# 01-POWER.net
KiCad netlist of a schematic drawn in Altium Designer
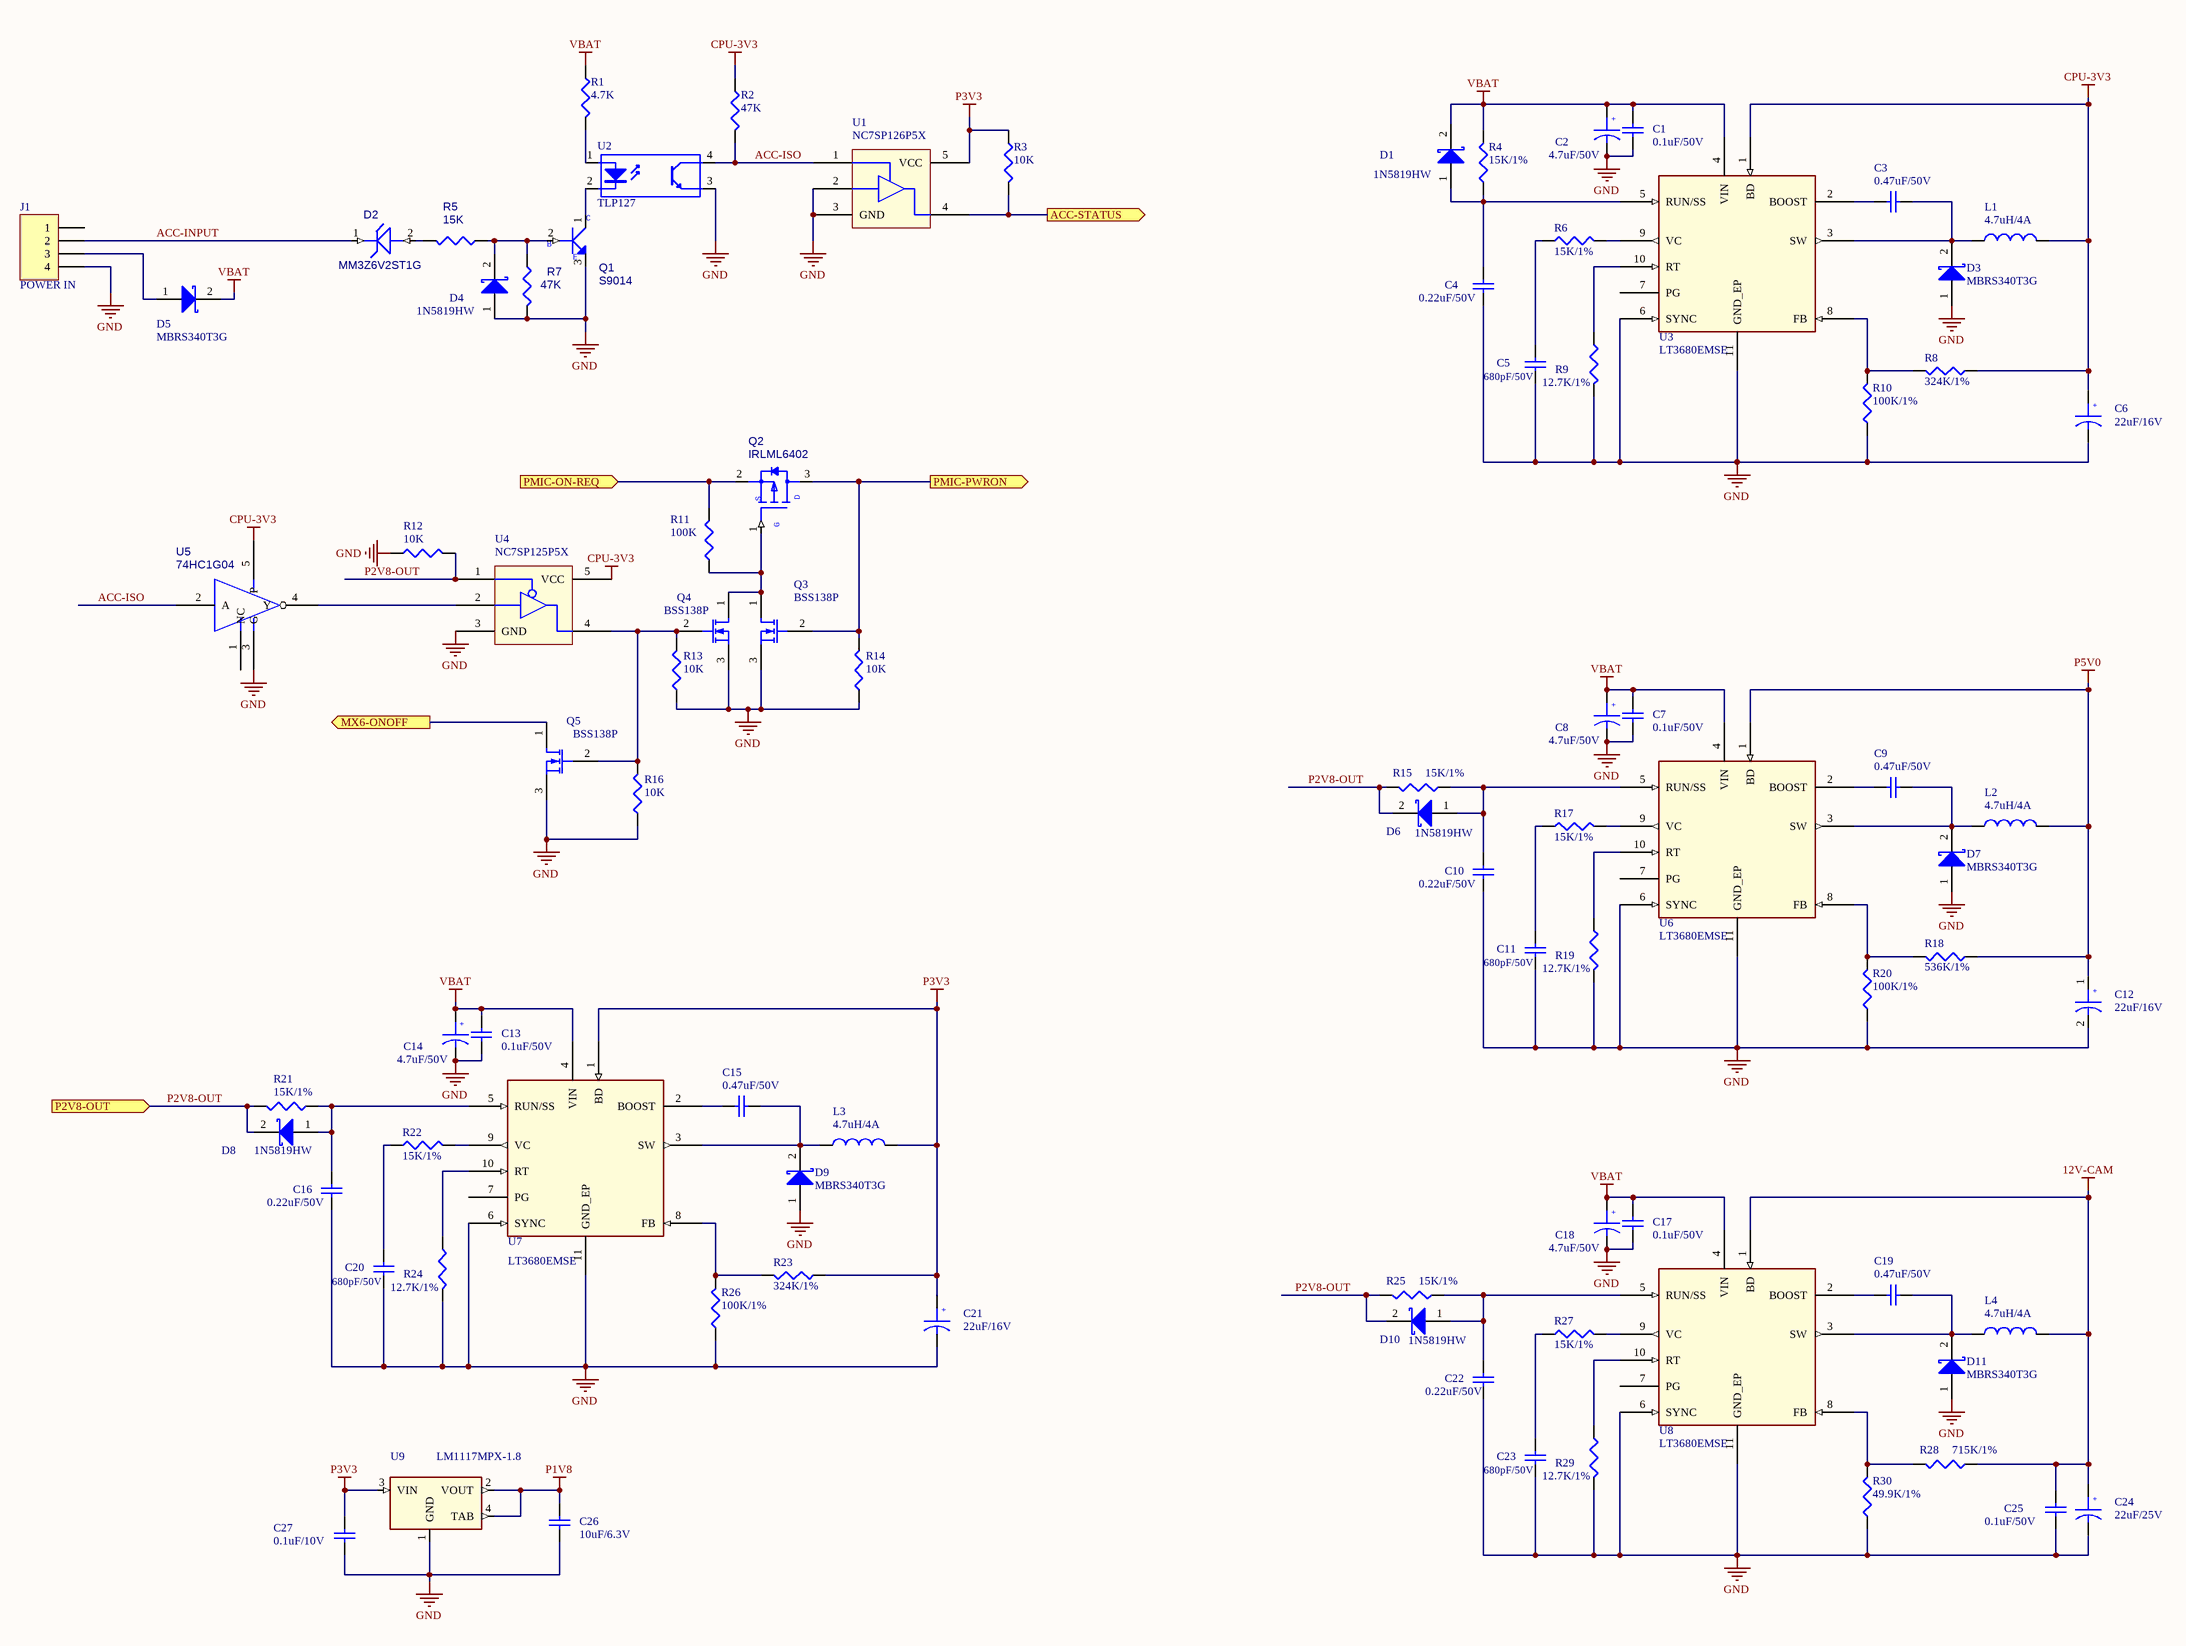
[diagram p0: 01-POWER.SchDoc]

(export (version "E")
  (design (tool "Eeschema 10.0.6"))
  (components
    (comp (ref "C1")
      (value "0.1uF/50V")
      (footprint "0603")
      (description "Capacitor")
      (fields (field (name "PUBLISHER") "Altium Limited"))
      (libsource (lib "Miscellaneous Devices") (part "Cap"))
    )
    (comp (ref "C2") (value "4.7uF/50V") (libsource (lib "*") (part "CAP WP")))
    (comp (ref "C3")
      (value "0.47uF/50V")
      (footprint "0603")
      (description "Capacitor")
      (fields (field (name "PUBLISHER") "Altium Limited"))
      (libsource (lib "Miscellaneous Devices") (part "Cap"))
    )
    (comp (ref "C4")
      (value "0.22uF/50V")
      (footprint "0603")
      (description "Capacitor")
      (fields (field (name "PUBLISHER") "Altium Limited"))
      (libsource (lib "Miscellaneous Devices") (part "Cap"))
    )
    (comp (ref "C5")
      (value "680pF/50V")
      (footprint "0402")
      (description "Capacitor")
      (fields (field (name "PUBLISHER") "Altium Limited"))
      (libsource (lib "Miscellaneous Devices") (part "Cap"))
    )
    (comp (ref "C6") (value "22uF/16V") (libsource (lib "*") (part "CAP WP")))
    (comp (ref "C7")
      (value "0.1uF/50V")
      (footprint "0603")
      (description "Capacitor")
      (fields (field (name "PUBLISHER") "Altium Limited"))
      (libsource (lib "Miscellaneous Devices") (part "Cap"))
    )
    (comp (ref "C8") (value "4.7uF/50V") (libsource (lib "*") (part "CAP WP")))
    (comp (ref "C9")
      (value "0.47uF/50V")
      (footprint "0603")
      (description "Capacitor")
      (fields (field (name "PUBLISHER") "Altium Limited"))
      (libsource (lib "Miscellaneous Devices") (part "Cap"))
    )
    (comp (ref "C10")
      (value "0.22uF/50V")
      (footprint "0603")
      (description "Capacitor")
      (fields (field (name "PUBLISHER") "Altium Limited"))
      (libsource (lib "Miscellaneous Devices") (part "Cap"))
    )
    (comp (ref "C11")
      (value "680pF/50V")
      (footprint "0402")
      (description "Capacitor")
      (fields (field (name "PUBLISHER") "Altium Limited"))
      (libsource (lib "Miscellaneous Devices") (part "Cap"))
    )
    (comp (ref "C12") (value "22uF/16V") (libsource (lib "") (part "CAP WP_1")))
    (comp (ref "C13")
      (value "0.1uF/50V")
      (footprint "0603")
      (description "Capacitor")
      (fields (field (name "PUBLISHER") "Altium Limited"))
      (libsource (lib "Miscellaneous Devices") (part "Cap"))
    )
    (comp (ref "C14") (value "4.7uF/50V") (libsource (lib "*") (part "CAP WP")))
    (comp (ref "C15")
      (value "0.47uF/50V")
      (footprint "0603")
      (description "Capacitor")
      (fields (field (name "PUBLISHER") "Altium Limited"))
      (libsource (lib "Miscellaneous Devices") (part "Cap"))
    )
    (comp (ref "C16")
      (value "0.22uF/50V")
      (footprint "0603")
      (description "Capacitor")
      (fields (field (name "PUBLISHER") "Altium Limited"))
      (libsource (lib "Miscellaneous Devices") (part "Cap"))
    )
    (comp (ref "C17")
      (value "0.1uF/50V")
      (footprint "0603")
      (description "Capacitor")
      (fields (field (name "PUBLISHER") "Altium Limited"))
      (libsource (lib "Miscellaneous Devices") (part "Cap"))
    )
    (comp (ref "C18") (value "4.7uF/50V") (libsource (lib "*") (part "CAP WP")))
    (comp (ref "C19")
      (value "0.47uF/50V")
      (footprint "0603")
      (description "Capacitor")
      (fields (field (name "PUBLISHER") "Altium Limited"))
      (libsource (lib "Miscellaneous Devices") (part "Cap"))
    )
    (comp (ref "C20")
      (value "680pF/50V")
      (footprint "0402")
      (description "Capacitor")
      (fields (field (name "PUBLISHER") "Altium Limited"))
      (libsource (lib "Miscellaneous Devices") (part "Cap"))
    )
    (comp (ref "C21") (value "22uF/16V") (libsource (lib "*") (part "CAP WP")))
    (comp (ref "C22")
      (value "0.22uF/50V")
      (footprint "0603")
      (description "Capacitor")
      (fields (field (name "PUBLISHER") "Altium Limited"))
      (libsource (lib "Miscellaneous Devices") (part "Cap"))
    )
    (comp (ref "C23")
      (value "680pF/50V")
      (footprint "0402")
      (description "Capacitor")
      (fields (field (name "PUBLISHER") "Altium Limited"))
      (libsource (lib "Miscellaneous Devices") (part "Cap"))
    )
    (comp (ref "C24") (value "22uF/25V") (libsource (lib "*") (part "CAP WP")))
    (comp (ref "C25")
      (value "0.1uF/50V")
      (footprint "0603")
      (description "Capacitor")
      (fields (field (name "PUBLISHER") "Altium Limited"))
      (libsource (lib "Miscellaneous Devices") (part "Cap"))
    )
    (comp (ref "C26")
      (value "10uF/6.3V")
      (footprint "0805")
      (description "Capacitor")
      (fields (field (name "PUBLISHER") "Altium Limited"))
      (libsource (lib "Miscellaneous Devices") (part "Cap"))
    )
    (comp (ref "C27")
      (value "0.1uF/10V")
      (footprint "0402")
      (description "Capacitor")
      (fields (field (name "PUBLISHER") "Altium Limited"))
      (libsource (lib "Miscellaneous Devices") (part "Cap"))
    )
    (comp (ref "D1")
      (value "1N5819HW")
      (footprint "1N5819")
      (description "Schottky Rectifier")
      (libsource (lib "Miscellaneous Devices") (part "Diode 11DQ03"))
    )
    (comp (ref "D2")
      (value "MM3Z6V2ST1G")
      (footprint "SOD323F")
      (libsource (lib "*") (part "MMGZ5231BPTLL34"))
    )
    (comp (ref "D3")
      (value "MBRS340T3G")
      (footprint "SMC")
      (description "Schottky Rectifier")
      (libsource (lib "Miscellaneous Devices") (part "Diode 11DQ03"))
    )
    (comp (ref "D4")
      (value "1N5819HW")
      (footprint "1N5819")
      (description "Schottky Rectifier")
      (libsource (lib "Miscellaneous Devices") (part "Diode 11DQ03"))
    )
    (comp (ref "D5")
      (value "MBRS340T3G")
      (footprint "SMC")
      (description "Schottky Rectifier")
      (libsource (lib "Miscellaneous Devices") (part "Diode 11DQ03"))
    )
    (comp (ref "D6")
      (value "1N5819HW")
      (footprint "1N5819")
      (description "Schottky Rectifier")
      (libsource (lib "Miscellaneous Devices") (part "Diode 11DQ03"))
    )
    (comp (ref "D7")
      (value "MBRS340T3G")
      (footprint "SMC")
      (description "Schottky Rectifier")
      (libsource (lib "Miscellaneous Devices") (part "Diode 11DQ03"))
    )
    (comp (ref "D8")
      (value "1N5819HW")
      (footprint "1N5819")
      (description "Schottky Rectifier")
      (libsource (lib "Miscellaneous Devices") (part "Diode 11DQ03"))
    )
    (comp (ref "D9")
      (value "MBRS340T3G")
      (footprint "SMC")
      (description "Schottky Rectifier")
      (libsource (lib "Miscellaneous Devices") (part "Diode 11DQ03"))
    )
    (comp (ref "D10")
      (value "1N5819HW")
      (footprint "1N5819")
      (description "Schottky Rectifier")
      (libsource (lib "Miscellaneous Devices") (part "Diode 11DQ03"))
    )
    (comp (ref "D11")
      (value "MBRS340T3G")
      (footprint "SMC")
      (description "Schottky Rectifier")
      (libsource (lib "Miscellaneous Devices") (part "Diode 11DQ03"))
    )
    (comp (ref "J1")
      (value "POWER IN")
      (footprint "3030WV-F-2*2P")
      (description "Header, 4-Pin")
      (fields (field (name "PUBLISHER") "Altium Limited"))
      (libsource (lib "Miscellaneous Connectors") (part "Header 4"))
    )
    (comp (ref "L1")
      (value "4.7uH/4A")
      (footprint "IND-10UH-1.5A")
      (description "IND CHK PWR 2.2UH@1MHZ 3.2A 20% SMT")
      (fields (field (name "TOLERANCE") "20%"))
      (libsource (lib "*") (part "INDUCTOR_A"))
    )
    (comp (ref "L2")
      (value "4.7uH/4A")
      (footprint "IND-10UH-1.5A")
      (description "IND CHK PWR 2.2UH@1MHZ 3.2A 20% SMT")
      (fields (field (name "TOLERANCE") "20%"))
      (libsource (lib "*") (part "INDUCTOR_A"))
    )
    (comp (ref "L3")
      (value "4.7uH/4A")
      (footprint "IND-10UH-1.5A")
      (description "IND CHK PWR 2.2UH@1MHZ 3.2A 20% SMT")
      (fields (field (name "TOLERANCE") "20%"))
      (libsource (lib "*") (part "INDUCTOR_A"))
    )
    (comp (ref "L4")
      (value "4.7uH/4A")
      (footprint "IND-10UH-1.5A")
      (description "IND CHK PWR 2.2UH@1MHZ 3.2A 20% SMT")
      (fields (field (name "TOLERANCE") "20%"))
      (libsource (lib "*") (part "INDUCTOR_A"))
    )
    (comp (ref "Q1")
      (value "S9014")
      (footprint "NPN")
      (fields (field (name "PART NUMBER") "SB039040000"))
      (libsource (lib "*") (part "MMBT3904_NL_SOT23-3"))
    )
    (comp (ref "Q2")
      (value "IRLML6402")
      (footprint "MOSFET")
      (fields (field (name "PART NUMBER") "SB934010010"))
      (libsource (lib "*") (part "AO3401L_SOT23-3_0"))
    )
    (comp (ref "Q3")
      (value "BSS138P")
      (footprint "NPN")
      (description "N-Channel MOSFET")
      (fields (field (name "PUBLISHER") "Altium Limited"))
      (libsource (lib "Miscellaneous Devices") (part "MOSFET-N"))
    )
    (comp (ref "Q4")
      (value "BSS138P")
      (footprint "NPN")
      (description "N-Channel MOSFET")
      (fields (field (name "PUBLISHER") "Altium Limited"))
      (libsource (lib "Miscellaneous Devices") (part "MOSFET-N"))
    )
    (comp (ref "Q5")
      (value "BSS138P")
      (footprint "NPN")
      (description "N-Channel MOSFET")
      (fields (field (name "PUBLISHER") "Altium Limited"))
      (libsource (lib "Miscellaneous Devices") (part "MOSFET-N"))
    )
    (comp (ref "R1") (value "4.7K") (footprint "0402") (libsource (lib "*") (part "CR16-1003FM")))
    (comp (ref "R2") (value "47K") (footprint "0402") (libsource (lib "*") (part "CR16-1003FM")))
    (comp (ref "R3") (value "10K") (footprint "0402") (libsource (lib "*") (part "CR16-1003FM")))
    (comp (ref "R4")
      (value "15K/1%")
      (footprint "0402")
      (description "Resistor")
      (fields (field (name "PUBLISHER") "Altium Limited"))
      (libsource (lib "Miscellaneous Devices") (part "Res3"))
    )
    (comp (ref "R5") (value "15K") (libsource (lib "*") (part "R")))
    (comp (ref "R6")
      (value "15K/1%")
      (footprint "0402")
      (description "Resistor")
      (fields (field (name "PUBLISHER") "Altium Limited"))
      (libsource (lib "Miscellaneous Devices") (part "Res3"))
    )
    (comp (ref "R7") (value "47K") (libsource (lib "*") (part "R")))
    (comp (ref "R8")
      (value "324K/1%")
      (footprint "0402")
      (description "Resistor")
      (fields (field (name "PUBLISHER") "Altium Limited"))
      (libsource (lib "Miscellaneous Devices") (part "Res3"))
    )
    (comp (ref "R9")
      (value "12.7K/1%")
      (footprint "0402")
      (description "Resistor")
      (fields (field (name "PUBLISHER") "Altium Limited"))
      (libsource (lib "Miscellaneous Devices") (part "Res3"))
    )
    (comp (ref "R10")
      (value "100K/1%")
      (footprint "0402")
      (description "Resistor")
      (fields (field (name "PUBLISHER") "Altium Limited"))
      (libsource (lib "Miscellaneous Devices") (part "Res3"))
    )
    (comp (ref "R11")
      (value "100K")
      (footprint "0402")
      (description "Resistor")
      (fields (field (name "PUBLISHER") "Altium Limited"))
      (libsource (lib "Miscellaneous Devices") (part "Res3"))
    )
    (comp (ref "R12") (value "10K") (footprint "0402") (libsource (lib "*") (part "CR16-1003FM")))
    (comp (ref "R13")
      (value "10K")
      (footprint "0402")
      (description "Resistor")
      (fields (field (name "PUBLISHER") "Altium Limited"))
      (libsource (lib "Miscellaneous Devices") (part "Res3"))
    )
    (comp (ref "R14")
      (value "10K")
      (footprint "0402")
      (description "Resistor")
      (fields (field (name "PUBLISHER") "Altium Limited"))
      (libsource (lib "Miscellaneous Devices") (part "Res3"))
    )
    (comp (ref "R15")
      (value "15K/1%")
      (footprint "0402")
      (description "Resistor")
      (fields (field (name "PUBLISHER") "Altium Limited"))
      (libsource (lib "Miscellaneous Devices") (part "Res3"))
    )
    (comp (ref "R16")
      (value "10K")
      (footprint "0402")
      (description "Resistor")
      (fields (field (name "PUBLISHER") "Altium Limited"))
      (libsource (lib "Miscellaneous Devices") (part "Res3"))
    )
    (comp (ref "R17")
      (value "15K/1%")
      (footprint "0402")
      (description "Resistor")
      (fields (field (name "PUBLISHER") "Altium Limited"))
      (libsource (lib "Miscellaneous Devices") (part "Res3"))
    )
    (comp (ref "R18")
      (value "536K/1%")
      (footprint "0402")
      (description "Resistor")
      (fields (field (name "PUBLISHER") "Altium Limited"))
      (libsource (lib "Miscellaneous Devices") (part "Res3"))
    )
    (comp (ref "R19")
      (value "12.7K/1%")
      (footprint "0402")
      (description "Resistor")
      (fields (field (name "PUBLISHER") "Altium Limited"))
      (libsource (lib "Miscellaneous Devices") (part "Res3"))
    )
    (comp (ref "R20")
      (value "100K/1%")
      (footprint "0402")
      (description "Resistor")
      (fields (field (name "PUBLISHER") "Altium Limited"))
      (libsource (lib "Miscellaneous Devices") (part "Res3"))
    )
    (comp (ref "R21")
      (value "15K/1%")
      (footprint "0402")
      (description "Resistor")
      (fields (field (name "PUBLISHER") "Altium Limited"))
      (libsource (lib "Miscellaneous Devices") (part "Res3"))
    )
    (comp (ref "R22")
      (value "15K/1%")
      (footprint "0402")
      (description "Resistor")
      (fields (field (name "PUBLISHER") "Altium Limited"))
      (libsource (lib "Miscellaneous Devices") (part "Res3"))
    )
    (comp (ref "R23")
      (value "324K/1%")
      (footprint "0402")
      (description "Resistor")
      (fields (field (name "PUBLISHER") "Altium Limited"))
      (libsource (lib "Miscellaneous Devices") (part "Res3"))
    )
    (comp (ref "R24")
      (value "12.7K/1%")
      (footprint "0402")
      (description "Resistor")
      (fields (field (name "PUBLISHER") "Altium Limited"))
      (libsource (lib "Miscellaneous Devices") (part "Res3"))
    )
    (comp (ref "R25")
      (value "15K/1%")
      (footprint "0402")
      (description "Resistor")
      (fields (field (name "PUBLISHER") "Altium Limited"))
      (libsource (lib "Miscellaneous Devices") (part "Res3"))
    )
    (comp (ref "R26")
      (value "100K/1%")
      (footprint "0402")
      (description "Resistor")
      (fields (field (name "PUBLISHER") "Altium Limited"))
      (libsource (lib "Miscellaneous Devices") (part "Res3"))
    )
    (comp (ref "R27")
      (value "15K/1%")
      (footprint "0402")
      (description "Resistor")
      (fields (field (name "PUBLISHER") "Altium Limited"))
      (libsource (lib "Miscellaneous Devices") (part "Res3"))
    )
    (comp (ref "R28")
      (value "715K/1%")
      (footprint "0402")
      (description "Resistor")
      (fields (field (name "PUBLISHER") "Altium Limited"))
      (libsource (lib "Miscellaneous Devices") (part "Res3"))
    )
    (comp (ref "R29")
      (value "12.7K/1%")
      (footprint "0402")
      (description "Resistor")
      (fields (field (name "PUBLISHER") "Altium Limited"))
      (libsource (lib "Miscellaneous Devices") (part "Res3"))
    )
    (comp (ref "R30")
      (value "49.9K/1%")
      (footprint "0402")
      (description "Resistor")
      (fields (field (name "PUBLISHER") "Altium Limited"))
      (libsource (lib "Miscellaneous Devices") (part "Res3"))
    )
    (comp (ref "U1") (value "NC7SP126P5X") (footprint "SC70") (libsource (lib "Schlib") (part "NC7SP126P5X")))
    (comp (ref "U2")
      (value "TLP127")
      (footprint "TLP127")
      (description "4-Pin Phototransistor Optocoupler")
      (fields (field (name "PUBLISHER") "Altium Limited"))
      (libsource (lib "Miscellaneous Devices") (part "Optoisolator1"))
    )
    (comp (ref "U3")
      (value "LT3680EMSE")
      (footprint "MSOP10")
      (description "IC VREG STEP DOWN SW 2.4MHZ 3.5A 0.79V-30V 3.6V-36V MSOP10")
      (libsource (lib "*") (part "LT3680_MSOP_10P"))
    )
    (comp (ref "U4") (value "NC7SP125P5X") (footprint "SC70") (libsource (lib "Schlib") (part "NC7SP125P5X")))
    (comp (ref "U5") (value "74HC1G04") (libsource (lib "*") (part "74LVC1G04GW_SOT353-5")))
    (comp (ref "U6")
      (value "LT3680EMSE")
      (footprint "MSOP10")
      (description "IC VREG STEP DOWN SW 2.4MHZ 3.5A 0.79V-30V 3.6V-36V MSOP10")
      (libsource (lib "*") (part "LT3680_MSOP_10P"))
    )
    (comp (ref "U7")
      (value "LT3680EMSE")
      (footprint "MSOP10")
      (description "IC VREG STEP DOWN SW 2.4MHZ 3.5A 0.79V-30V 3.6V-36V MSOP10")
      (libsource (lib "*") (part "LT3680_MSOP_10P"))
    )
    (comp (ref "U8")
      (value "LT3680EMSE")
      (footprint "MSOP10")
      (description "IC VREG STEP DOWN SW 2.4MHZ 3.5A 0.79V-30V 3.6V-36V MSOP10")
      (libsource (lib "*") (part "LT3680_MSOP_10P"))
    )
    (comp (ref "U9")
      (value "LM1117MPX-1.8")
      (footprint "AMS1117")
      (description "IC VREG LDO 1.8V 1A 10V SOT-223")
      (libsource (lib "*") (part "LD1117AS18"))
    )
  )
  (nets
    (net (code "1") (name "/ACC-INPUT") (class "Default")
      (node (ref "D2") (pin "1") (pinfunction "1_1") (pintype "input"))
      (node (ref "J1") (pin "2") (pinfunction "2_2") (pintype "passive"))
    )
    (net (code "2") (name "/ACC-ISO") (class "Default")
      (node (ref "R2") (pin "2") (pinfunction "2_2") (pintype "passive"))
      (node (ref "U1") (pin "1") (pinfunction "OE_1") (pintype "passive"))
      (node (ref "U2") (pin "4") (pinfunction "C_4") (pintype "passive"))
      (node (ref "U5") (pin "2") (pinfunction "A_2") (pintype "passive"))
    )
    (net (code "3") (name "/ACC-STATUS") (class "Default")
      (node (ref "R3") (pin "2") (pinfunction "2_2") (pintype "passive"))
      (node (ref "U1") (pin "4") (pinfunction "Y_4") (pintype "passive"))
    )
    (net (code "4") (name "/MX6-ONOFF") (class "Default")
      (node (ref "Q5") (pin "1") (pinfunction "D_1") (pintype "passive"))
    )
    (net (code "5") (name "/P2V8-OUT") (class "Default")
      (node (ref "D10") (pin "2") (pinfunction "K_2") (pintype "passive"))
      (node (ref "D6") (pin "2") (pinfunction "K_2") (pintype "passive"))
      (node (ref "D8") (pin "2") (pinfunction "K_2") (pintype "passive"))
      (node (ref "R12") (pin "1") (pinfunction "1_1") (pintype "passive"))
      (node (ref "R15") (pin "2") (pinfunction "2_2") (pintype "passive"))
      (node (ref "R21") (pin "2") (pinfunction "2_2") (pintype "passive"))
      (node (ref "R25") (pin "2") (pinfunction "2_2") (pintype "passive"))
      (node (ref "U4") (pin "1") (pinfunction "OE_1") (pintype "passive"))
    )
    (net (code "6") (name "/PMIC-ON-REQ") (class "Default")
      (node (ref "Q2") (pin "2") (pinfunction "S_2") (pintype "passive"))
      (node (ref "R11") (pin "1") (pinfunction "1_1") (pintype "passive"))
    )
    (net (code "7") (name "/PMIC-PWRON") (class "Default")
      (node (ref "Q2") (pin "3") (pinfunction "D_3") (pintype "passive"))
      (node (ref "Q3") (pin "2") (pinfunction "G_2") (pintype "passive"))
      (node (ref "R14") (pin "1") (pinfunction "1_1") (pintype "passive"))
    )
    (net (code "8") (name "12V-CAM") (class "Default")
      (node (ref "C24") (pin "1") (pinfunction "1_1") (pintype "passive"))
      (node (ref "C25") (pin "1") (pinfunction "1_1") (pintype "passive"))
      (node (ref "L4") (pin "2") (pinfunction "2_2") (pintype "passive"))
      (node (ref "R28") (pin "1") (pinfunction "1_1") (pintype "passive"))
      (node (ref "U8") (pin "1") (pinfunction "BD_1") (pintype "input"))
    )
    (net (code "9") (name "CPU-3V3") (class "Default")
      (node (ref "C6") (pin "1") (pinfunction "1_1") (pintype "passive"))
      (node (ref "L1") (pin "2") (pinfunction "2_2") (pintype "passive"))
      (node (ref "R2") (pin "1") (pinfunction "1_1") (pintype "passive"))
      (node (ref "R8") (pin "1") (pinfunction "1_1") (pintype "passive"))
      (node (ref "U3") (pin "1") (pinfunction "BD_1") (pintype "input"))
      (node (ref "U4") (pin "5") (pinfunction "VCC_5") (pintype "passive"))
      (node (ref "U5") (pin "5") (pinfunction "P_5") (pintype "passive"))
    )
    (net (code "10") (name "GND") (class "Default")
      (node (ref "C1") (pin "2") (pinfunction "2_2") (pintype "passive"))
      (node (ref "C10") (pin "2") (pinfunction "2_2") (pintype "passive"))
      (node (ref "C11") (pin "2") (pinfunction "2_2") (pintype "passive"))
      (node (ref "C12") (pin "2") (pinfunction "2_2") (pintype "passive"))
      (node (ref "C13") (pin "2") (pinfunction "2_2") (pintype "passive"))
      (node (ref "C14") (pin "2") (pinfunction "2_2") (pintype "passive"))
      (node (ref "C16") (pin "2") (pinfunction "2_2") (pintype "passive"))
      (node (ref "C17") (pin "2") (pinfunction "2_2") (pintype "passive"))
      (node (ref "C18") (pin "2") (pinfunction "2_2") (pintype "passive"))
      (node (ref "C2") (pin "2") (pinfunction "2_2") (pintype "passive"))
      (node (ref "C20") (pin "2") (pinfunction "2_2") (pintype "passive"))
      (node (ref "C21") (pin "2") (pinfunction "2_2") (pintype "passive"))
      (node (ref "C22") (pin "2") (pinfunction "2_2") (pintype "passive"))
      (node (ref "C23") (pin "2") (pinfunction "2_2") (pintype "passive"))
      (node (ref "C24") (pin "2") (pinfunction "2_2") (pintype "passive"))
      (node (ref "C25") (pin "2") (pinfunction "2_2") (pintype "passive"))
      (node (ref "C26") (pin "2") (pinfunction "2_2") (pintype "passive"))
      (node (ref "C27") (pin "2") (pinfunction "2_2") (pintype "passive"))
      (node (ref "C4") (pin "2") (pinfunction "2_2") (pintype "passive"))
      (node (ref "C5") (pin "2") (pinfunction "2_2") (pintype "passive"))
      (node (ref "C6") (pin "2") (pinfunction "2_2") (pintype "passive"))
      (node (ref "C7") (pin "2") (pinfunction "2_2") (pintype "passive"))
      (node (ref "C8") (pin "2") (pinfunction "2_2") (pintype "passive"))
      (node (ref "D11") (pin "1") (pinfunction "A_1") (pintype "passive"))
      (node (ref "D3") (pin "1") (pinfunction "A_1") (pintype "passive"))
      (node (ref "D4") (pin "1") (pinfunction "A_1") (pintype "passive"))
      (node (ref "D7") (pin "1") (pinfunction "A_1") (pintype "passive"))
      (node (ref "D9") (pin "1") (pinfunction "A_1") (pintype "passive"))
      (node (ref "J1") (pin "4") (pinfunction "4_4") (pintype "passive"))
      (node (ref "Q1") (pin "3") (pinfunction "EMITTER_3") (pintype "passive"))
      (node (ref "Q3") (pin "3") (pinfunction "S_3") (pintype "passive"))
      (node (ref "Q4") (pin "3") (pinfunction "S_3") (pintype "passive"))
      (node (ref "Q5") (pin "3") (pinfunction "S_3") (pintype "passive"))
      (node (ref "R10") (pin "1") (pinfunction "1_1") (pintype "passive"))
      (node (ref "R12") (pin "2") (pinfunction "2_2") (pintype "passive"))
      (node (ref "R13") (pin "2") (pinfunction "2_2") (pintype "passive"))
      (node (ref "R14") (pin "2") (pinfunction "2_2") (pintype "passive"))
      (node (ref "R16") (pin "2") (pinfunction "2_2") (pintype "passive"))
      (node (ref "R19") (pin "2") (pinfunction "2_2") (pintype "passive"))
      (node (ref "R20") (pin "1") (pinfunction "1_1") (pintype "passive"))
      (node (ref "R24") (pin "2") (pinfunction "2_2") (pintype "passive"))
      (node (ref "R26") (pin "1") (pinfunction "1_1") (pintype "passive"))
      (node (ref "R29") (pin "2") (pinfunction "2_2") (pintype "passive"))
      (node (ref "R30") (pin "1") (pinfunction "1_1") (pintype "passive"))
      (node (ref "R7") (pin "2") (pinfunction "2_2") (pintype "passive"))
      (node (ref "R9") (pin "2") (pinfunction "2_2") (pintype "passive"))
      (node (ref "U1") (pin "2") (pinfunction "A_2") (pintype "passive"))
      (node (ref "U1") (pin "3") (pinfunction "GND_3") (pintype "passive"))
      (node (ref "U2") (pin "3") (pinfunction "E_3") (pintype "passive"))
      (node (ref "U3") (pin "11") (pinfunction "GND_EP_11") (pintype "power_in"))
      (node (ref "U3") (pin "6") (pinfunction "SYNC_6") (pintype "input"))
      (node (ref "U4") (pin "3") (pinfunction "GND_3") (pintype "passive"))
      (node (ref "U5") (pin "3") (pinfunction "G_3") (pintype "passive"))
      (node (ref "U6") (pin "11") (pinfunction "GND_EP_11") (pintype "power_in"))
      (node (ref "U6") (pin "6") (pinfunction "SYNC_6") (pintype "input"))
      (node (ref "U7") (pin "11") (pinfunction "GND_EP_11") (pintype "power_in"))
      (node (ref "U7") (pin "6") (pinfunction "SYNC_6") (pintype "input"))
      (node (ref "U8") (pin "11") (pinfunction "GND_EP_11") (pintype "power_in"))
      (node (ref "U8") (pin "6") (pinfunction "SYNC_6") (pintype "input"))
      (node (ref "U9") (pin "1") (pinfunction "GND_1") (pintype "power_in"))
    )
    (net (code "11") (name "Net-(C5-Pad1)") (class "Default")
      (node (ref "C5") (pin "1") (pinfunction "1_1") (pintype "passive"))
      (node (ref "R6") (pin "1") (pinfunction "1_1") (pintype "passive"))
    )
    (net (code "12") (name "Net-(C11-Pad1)") (class "Default")
      (node (ref "C11") (pin "1") (pinfunction "1_1") (pintype "passive"))
      (node (ref "R17") (pin "1") (pinfunction "1_1") (pintype "passive"))
    )
    (net (code "13") (name "Net-(C20-Pad1)") (class "Default")
      (node (ref "C20") (pin "1") (pinfunction "1_1") (pintype "passive"))
      (node (ref "R22") (pin "1") (pinfunction "1_1") (pintype "passive"))
    )
    (net (code "14") (name "Net-(C23-Pad1)") (class "Default")
      (node (ref "C23") (pin "1") (pinfunction "1_1") (pintype "passive"))
      (node (ref "R27") (pin "1") (pinfunction "1_1") (pintype "passive"))
    )
    (net (code "15") (name "Net-(D1-A)") (class "Default")
      (node (ref "C4") (pin "1") (pinfunction "1_1") (pintype "passive"))
      (node (ref "D1") (pin "1") (pinfunction "A_1") (pintype "passive"))
      (node (ref "R4") (pin "1") (pinfunction "1_1") (pintype "passive"))
      (node (ref "U3") (pin "5") (pinfunction "RUN/SS_5") (pintype "input"))
    )
    (net (code "16") (name "Net-(D2-Pad2)") (class "Default")
      (node (ref "D2") (pin "2") (pinfunction "2_2") (pintype "input"))
      (node (ref "R5") (pin "2") (pinfunction "2_2") (pintype "passive"))
    )
    (net (code "17") (name "Net-(D3-K)") (class "Default")
      (node (ref "C3") (pin "1") (pinfunction "1_1") (pintype "passive"))
      (node (ref "D3") (pin "2") (pinfunction "K_2") (pintype "passive"))
      (node (ref "L1") (pin "1") (pinfunction "1_1") (pintype "passive"))
      (node (ref "U3") (pin "3") (pinfunction "SW_3") (pintype "output"))
    )
    (net (code "18") (name "Net-(D4-K)") (class "Default")
      (node (ref "D4") (pin "2") (pinfunction "K_2") (pintype "passive"))
      (node (ref "Q1") (pin "2") (pinfunction "BASE_2") (pintype "input"))
      (node (ref "R5") (pin "1") (pinfunction "1_1") (pintype "passive"))
      (node (ref "R7") (pin "1") (pinfunction "1_1") (pintype "passive"))
    )
    (net (code "19") (name "Net-(D5-A)") (class "Default")
      (node (ref "D5") (pin "1") (pinfunction "A_1") (pintype "passive"))
      (node (ref "J1") (pin "3") (pinfunction "3_3") (pintype "passive"))
    )
    (net (code "20") (name "Net-(D6-A)") (class "Default")
      (node (ref "C10") (pin "1") (pinfunction "1_1") (pintype "passive"))
      (node (ref "D6") (pin "1") (pinfunction "A_1") (pintype "passive"))
      (node (ref "R15") (pin "1") (pinfunction "1_1") (pintype "passive"))
      (node (ref "U6") (pin "5") (pinfunction "RUN/SS_5") (pintype "input"))
    )
    (net (code "21") (name "Net-(D7-K)") (class "Default")
      (node (ref "C9") (pin "1") (pinfunction "1_1") (pintype "passive"))
      (node (ref "D7") (pin "2") (pinfunction "K_2") (pintype "passive"))
      (node (ref "L2") (pin "1") (pinfunction "1_1") (pintype "passive"))
      (node (ref "U6") (pin "3") (pinfunction "SW_3") (pintype "output"))
    )
    (net (code "22") (name "Net-(D8-A)") (class "Default")
      (node (ref "C16") (pin "1") (pinfunction "1_1") (pintype "passive"))
      (node (ref "D8") (pin "1") (pinfunction "A_1") (pintype "passive"))
      (node (ref "R21") (pin "1") (pinfunction "1_1") (pintype "passive"))
      (node (ref "U7") (pin "5") (pinfunction "RUN/SS_5") (pintype "input"))
    )
    (net (code "23") (name "Net-(D9-K)") (class "Default")
      (node (ref "C15") (pin "1") (pinfunction "1_1") (pintype "passive"))
      (node (ref "D9") (pin "2") (pinfunction "K_2") (pintype "passive"))
      (node (ref "L3") (pin "1") (pinfunction "1_1") (pintype "passive"))
      (node (ref "U7") (pin "3") (pinfunction "SW_3") (pintype "output"))
    )
    (net (code "24") (name "Net-(D10-A)") (class "Default")
      (node (ref "C22") (pin "1") (pinfunction "1_1") (pintype "passive"))
      (node (ref "D10") (pin "1") (pinfunction "A_1") (pintype "passive"))
      (node (ref "R25") (pin "1") (pinfunction "1_1") (pintype "passive"))
      (node (ref "U8") (pin "5") (pinfunction "RUN/SS_5") (pintype "input"))
    )
    (net (code "25") (name "Net-(D11-K)") (class "Default")
      (node (ref "C19") (pin "1") (pinfunction "1_1") (pintype "passive"))
      (node (ref "D11") (pin "2") (pinfunction "K_2") (pintype "passive"))
      (node (ref "L4") (pin "1") (pinfunction "1_1") (pintype "passive"))
      (node (ref "U8") (pin "3") (pinfunction "SW_3") (pintype "output"))
    )
    (net (code "26") (name "Net-(Q1-COLLECTOR)") (class "Default")
      (node (ref "Q1") (pin "1") (pinfunction "COLLECTOR_1") (pintype "passive"))
      (node (ref "U2") (pin "2") (pinfunction "K_2") (pintype "passive"))
    )
    (net (code "27") (name "Net-(Q2-G)") (class "Default")
      (node (ref "Q2") (pin "1") (pinfunction "G_1") (pintype "input"))
      (node (ref "Q3") (pin "1") (pinfunction "D_1") (pintype "passive"))
      (node (ref "Q4") (pin "1") (pinfunction "D_1") (pintype "passive"))
      (node (ref "R11") (pin "2") (pinfunction "2_2") (pintype "passive"))
    )
    (net (code "28") (name "Net-(Q4-G)") (class "Default")
      (node (ref "Q4") (pin "2") (pinfunction "G_2") (pintype "passive"))
      (node (ref "Q5") (pin "2") (pinfunction "G_2") (pintype "passive"))
      (node (ref "R13") (pin "1") (pinfunction "1_1") (pintype "passive"))
      (node (ref "R16") (pin "1") (pinfunction "1_1") (pintype "passive"))
      (node (ref "U4") (pin "4") (pinfunction "Y_4") (pintype "passive"))
    )
    (net (code "29") (name "Net-(U2-A)") (class "Default")
      (node (ref "R1") (pin "2") (pinfunction "2_2") (pintype "passive"))
      (node (ref "U2") (pin "1") (pinfunction "A_1") (pintype "passive"))
    )
    (net (code "30") (name "Net-(U3-BOOST)") (class "Default")
      (node (ref "C3") (pin "2") (pinfunction "2_2") (pintype "passive"))
      (node (ref "U3") (pin "2") (pinfunction "BOOST_2") (pintype "power_in"))
    )
    (net (code "31") (name "Net-(U3-FB)") (class "Default")
      (node (ref "R10") (pin "2") (pinfunction "2_2") (pintype "passive"))
      (node (ref "R8") (pin "2") (pinfunction "2_2") (pintype "passive"))
      (node (ref "U3") (pin "8") (pinfunction "FB_8") (pintype "input"))
    )
    (net (code "32") (name "Net-(U3-RT)") (class "Default")
      (node (ref "R9") (pin "1") (pinfunction "1_1") (pintype "passive"))
      (node (ref "U3") (pin "10") (pinfunction "RT_10") (pintype "input"))
    )
    (net (code "33") (name "Net-(U3-VC)") (class "Default")
      (node (ref "R6") (pin "2") (pinfunction "2_2") (pintype "passive"))
      (node (ref "U3") (pin "9") (pinfunction "VC_9") (pintype "output"))
    )
    (net (code "34") (name "Net-(U4-A)") (class "Default")
      (node (ref "U4") (pin "2") (pinfunction "A_2") (pintype "passive"))
      (node (ref "U5") (pin "4") (pinfunction "Y_4") (pintype "passive"))
    )
    (net (code "35") (name "Net-(U6-BOOST)") (class "Default")
      (node (ref "C9") (pin "2") (pinfunction "2_2") (pintype "passive"))
      (node (ref "U6") (pin "2") (pinfunction "BOOST_2") (pintype "power_in"))
    )
    (net (code "36") (name "Net-(U6-FB)") (class "Default")
      (node (ref "R18") (pin "2") (pinfunction "2_2") (pintype "passive"))
      (node (ref "R20") (pin "2") (pinfunction "2_2") (pintype "passive"))
      (node (ref "U6") (pin "8") (pinfunction "FB_8") (pintype "input"))
    )
    (net (code "37") (name "Net-(U6-RT)") (class "Default")
      (node (ref "R19") (pin "1") (pinfunction "1_1") (pintype "passive"))
      (node (ref "U6") (pin "10") (pinfunction "RT_10") (pintype "input"))
    )
    (net (code "38") (name "Net-(U6-VC)") (class "Default")
      (node (ref "R17") (pin "2") (pinfunction "2_2") (pintype "passive"))
      (node (ref "U6") (pin "9") (pinfunction "VC_9") (pintype "output"))
    )
    (net (code "39") (name "Net-(U7-BOOST)") (class "Default")
      (node (ref "C15") (pin "2") (pinfunction "2_2") (pintype "passive"))
      (node (ref "U7") (pin "2") (pinfunction "BOOST_2") (pintype "power_in"))
    )
    (net (code "40") (name "Net-(U7-FB)") (class "Default")
      (node (ref "R23") (pin "2") (pinfunction "2_2") (pintype "passive"))
      (node (ref "R26") (pin "2") (pinfunction "2_2") (pintype "passive"))
      (node (ref "U7") (pin "8") (pinfunction "FB_8") (pintype "input"))
    )
    (net (code "41") (name "Net-(U7-RT)") (class "Default")
      (node (ref "R24") (pin "1") (pinfunction "1_1") (pintype "passive"))
      (node (ref "U7") (pin "10") (pinfunction "RT_10") (pintype "input"))
    )
    (net (code "42") (name "Net-(U7-VC)") (class "Default")
      (node (ref "R22") (pin "2") (pinfunction "2_2") (pintype "passive"))
      (node (ref "U7") (pin "9") (pinfunction "VC_9") (pintype "output"))
    )
    (net (code "43") (name "Net-(U8-BOOST)") (class "Default")
      (node (ref "C19") (pin "2") (pinfunction "2_2") (pintype "passive"))
      (node (ref "U8") (pin "2") (pinfunction "BOOST_2") (pintype "power_in"))
    )
    (net (code "44") (name "Net-(U8-FB)") (class "Default")
      (node (ref "R28") (pin "2") (pinfunction "2_2") (pintype "passive"))
      (node (ref "R30") (pin "2") (pinfunction "2_2") (pintype "passive"))
      (node (ref "U8") (pin "8") (pinfunction "FB_8") (pintype "input"))
    )
    (net (code "45") (name "Net-(U8-RT)") (class "Default")
      (node (ref "R29") (pin "1") (pinfunction "1_1") (pintype "passive"))
      (node (ref "U8") (pin "10") (pinfunction "RT_10") (pintype "input"))
    )
    (net (code "46") (name "Net-(U8-VC)") (class "Default")
      (node (ref "R27") (pin "2") (pinfunction "2_2") (pintype "passive"))
      (node (ref "U8") (pin "9") (pinfunction "VC_9") (pintype "output"))
    )
    (net (code "47") (name "P1V8") (class "Default")
      (node (ref "C26") (pin "1") (pinfunction "1_1") (pintype "passive"))
      (node (ref "U9") (pin "2") (pinfunction "VOUT_2") (pintype "output"))
      (node (ref "U9") (pin "4") (pinfunction "TAB_4") (pintype "output"))
    )
    (net (code "48") (name "P3V3") (class "Default")
      (node (ref "C21") (pin "1") (pinfunction "1_1") (pintype "passive"))
      (node (ref "C27") (pin "1") (pinfunction "1_1") (pintype "passive"))
      (node (ref "L3") (pin "2") (pinfunction "2_2") (pintype "passive"))
      (node (ref "R23") (pin "1") (pinfunction "1_1") (pintype "passive"))
      (node (ref "R3") (pin "1") (pinfunction "1_1") (pintype "passive"))
      (node (ref "U1") (pin "5") (pinfunction "VCC_5") (pintype "passive"))
      (node (ref "U7") (pin "1") (pinfunction "BD_1") (pintype "input"))
      (node (ref "U9") (pin "3") (pinfunction "VIN_3") (pintype "input"))
    )
    (net (code "49") (name "P5V0") (class "Default")
      (node (ref "C12") (pin "1") (pinfunction "1_1") (pintype "passive"))
      (node (ref "L2") (pin "2") (pinfunction "2_2") (pintype "passive"))
      (node (ref "R18") (pin "1") (pinfunction "1_1") (pintype "passive"))
      (node (ref "U6") (pin "1") (pinfunction "BD_1") (pintype "input"))
    )
    (net (code "50") (name "VBAT") (class "Default")
      (node (ref "C1") (pin "1") (pinfunction "1_1") (pintype "passive"))
      (node (ref "C13") (pin "1") (pinfunction "1_1") (pintype "passive"))
      (node (ref "C14") (pin "1") (pinfunction "1_1") (pintype "passive"))
      (node (ref "C17") (pin "1") (pinfunction "1_1") (pintype "passive"))
      (node (ref "C18") (pin "1") (pinfunction "1_1") (pintype "passive"))
      (node (ref "C2") (pin "1") (pinfunction "1_1") (pintype "passive"))
      (node (ref "C7") (pin "1") (pinfunction "1_1") (pintype "passive"))
      (node (ref "C8") (pin "1") (pinfunction "1_1") (pintype "passive"))
      (node (ref "D1") (pin "2") (pinfunction "K_2") (pintype "passive"))
      (node (ref "D5") (pin "2") (pinfunction "K_2") (pintype "passive"))
      (node (ref "R1") (pin "1") (pinfunction "1_1") (pintype "passive"))
      (node (ref "R4") (pin "2") (pinfunction "2_2") (pintype "passive"))
      (node (ref "U3") (pin "4") (pinfunction "VIN_4") (pintype "power_in"))
      (node (ref "U6") (pin "4") (pinfunction "VIN_4") (pintype "power_in"))
      (node (ref "U7") (pin "4") (pinfunction "VIN_4") (pintype "power_in"))
      (node (ref "U8") (pin "4") (pinfunction "VIN_4") (pintype "power_in"))
    )
    (net (code "51") (name "unconnected-(J1-Pad1)") (class "Default")
      (node (ref "J1") (pin "1") (pinfunction "1_1") (pintype "passive"))
    )
    (net (code "52") (name "unconnected-(U3-PG-Pad7)") (class "Default")
      (node (ref "U3") (pin "7") (pinfunction "PG_7") (pintype "open_collector"))
    )
    (net (code "53") (name "unconnected-(U5-NC-Pad1)") (class "Default")
      (node (ref "U5") (pin "1") (pinfunction "NC_1") (pintype "passive"))
    )
    (net (code "54") (name "unconnected-(U6-PG-Pad7)") (class "Default")
      (node (ref "U6") (pin "7") (pinfunction "PG_7") (pintype "open_collector"))
    )
    (net (code "55") (name "unconnected-(U7-PG-Pad7)") (class "Default")
      (node (ref "U7") (pin "7") (pinfunction "PG_7") (pintype "open_collector"))
    )
    (net (code "56") (name "unconnected-(U8-PG-Pad7)") (class "Default")
      (node (ref "U8") (pin "7") (pinfunction "PG_7") (pintype "open_collector"))
    )
  )
)
